# 8161_-FSK_V1_26.net
KiCad netlist of a schematic drawn in Altium Designer
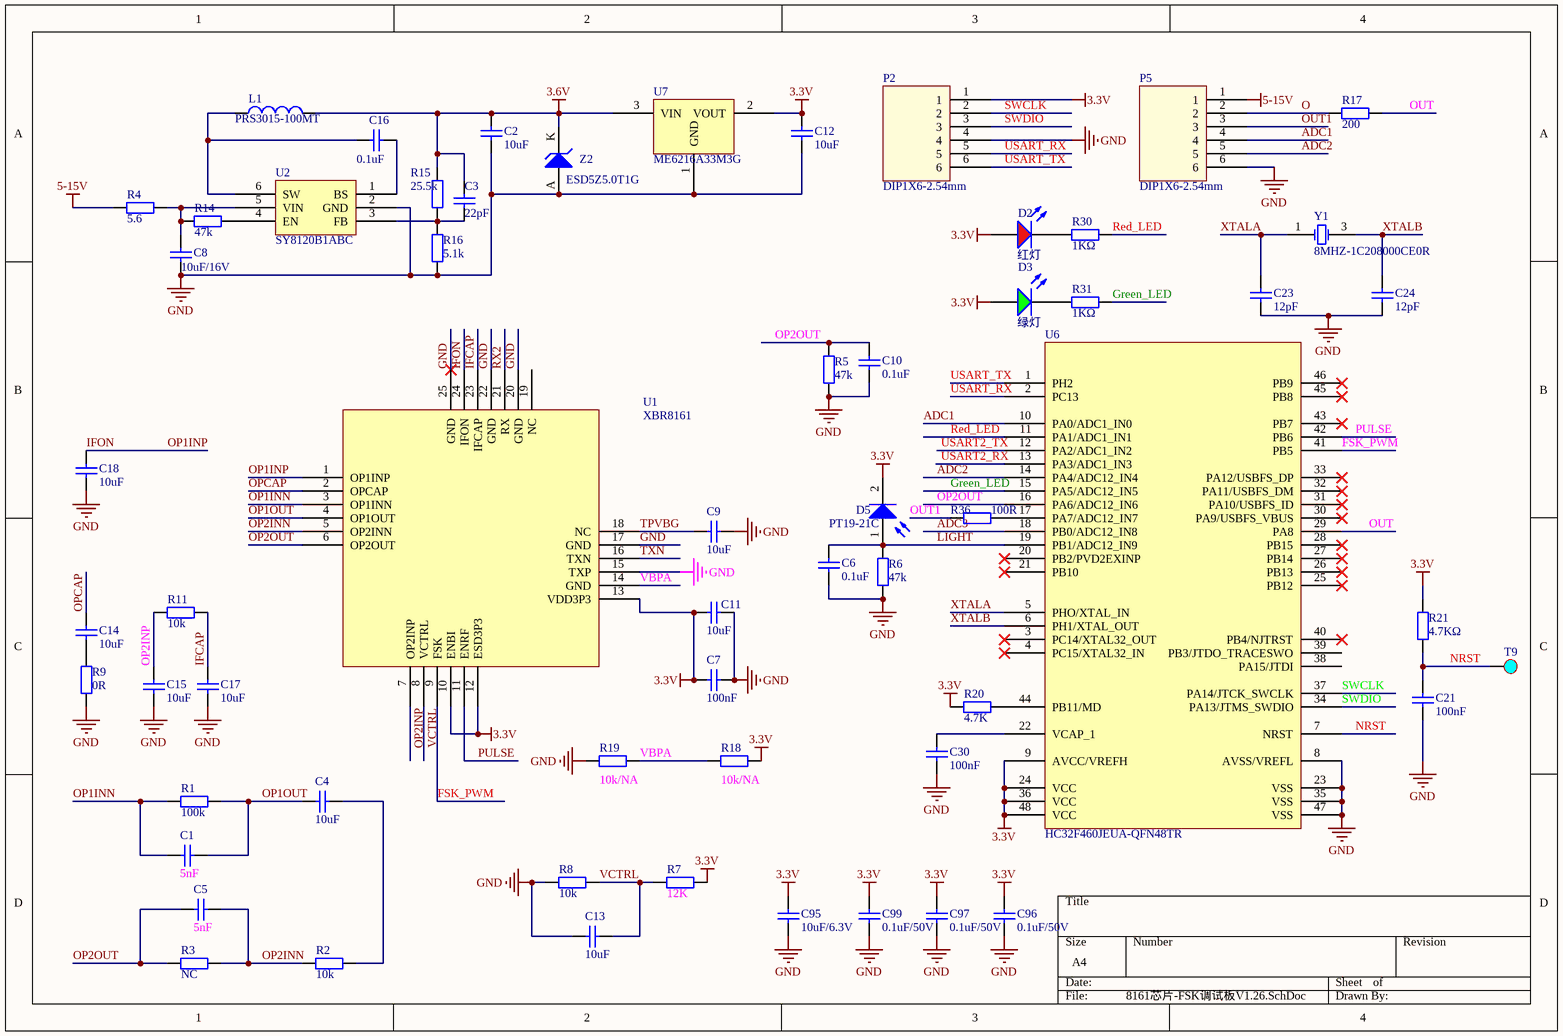
[diagram p0: 8161芯片-FSK调试板V1.26.SchDoc]

(export (version "E")
  (design (tool "Eeschema 10.0.6"))
  (components
    (comp (ref "C1")
      (value "5nF")
      (footprint "C0402")
      (description "Capacitor")
      (fields (field (name "PUBLISHER") "Altium Limited"))
      (libsource (lib "Miscellaneous Devices") (part "Cap"))
    )
    (comp (ref "C2")
      (value "10uF")
      (footprint "C0402")
      (description "Capacitor")
      (fields (field (name "PUBLISHER") "Altium Limited"))
      (libsource (lib "Miscellaneous Devices") (part "Cap"))
    )
    (comp (ref "C3")
      (value "22pF")
      (footprint "C0402")
      (description "Capacitor")
      (fields (field (name "PUBLISHER") "Altium Limited"))
      (libsource (lib "Miscellaneous Devices") (part "Cap"))
    )
    (comp (ref "C4")
      (value "10uF")
      (footprint "C0402")
      (description "Capacitor")
      (fields (field (name "PUBLISHER") "Altium Limited"))
      (libsource (lib "Miscellaneous Devices") (part "Cap"))
    )
    (comp (ref "C5")
      (value "5nF")
      (footprint "C0402")
      (description "Capacitor")
      (fields (field (name "PUBLISHER") "Altium Limited"))
      (libsource (lib "Miscellaneous Devices") (part "Cap"))
    )
    (comp (ref "C6")
      (value "0.1uF")
      (footprint "C0402")
      (description "Capacitor")
      (fields (field (name "PUBLISHER") "Altium Limited"))
      (libsource (lib "Miscellaneous Devices") (part "Cap"))
    )
    (comp (ref "C7")
      (value "100nF")
      (footprint "C0402")
      (description "Capacitor")
      (fields (field (name "PUBLISHER") "Altium Limited"))
      (libsource (lib "Miscellaneous Devices") (part "Cap"))
    )
    (comp (ref "C8")
      (value "10uF/16V")
      (footprint "C0603")
      (description "Capacitor")
      (fields (field (name "PUBLISHER") "Altium Limited"))
      (libsource (lib "Miscellaneous Devices") (part "Cap"))
    )
    (comp (ref "C9")
      (value "10uF")
      (footprint "C0402")
      (description "Capacitor")
      (fields (field (name "PUBLISHER") "Altium Limited"))
      (libsource (lib "Miscellaneous Devices") (part "Cap"))
    )
    (comp (ref "C10")
      (value "0.1uF")
      (footprint "C0402")
      (description "Capacitor")
      (fields (field (name "PUBLISHER") "Altium Limited"))
      (libsource (lib "Miscellaneous Devices") (part "Cap"))
    )
    (comp (ref "C11")
      (value "10uF")
      (footprint "C0402")
      (description "Capacitor")
      (fields (field (name "PUBLISHER") "Altium Limited"))
      (libsource (lib "Miscellaneous Devices") (part "Cap"))
    )
    (comp (ref "C12")
      (value "10uF")
      (footprint "C0402")
      (description "Capacitor")
      (fields (field (name "PUBLISHER") "Altium Limited"))
      (libsource (lib "Miscellaneous Devices") (part "Cap"))
    )
    (comp (ref "C13")
      (value "10uF")
      (footprint "C0402")
      (description "Capacitor")
      (fields (field (name "PUBLISHER") "Altium Limited"))
      (libsource (lib "Miscellaneous Devices") (part "Cap"))
    )
    (comp (ref "C14")
      (value "10uF")
      (footprint "C0402")
      (description "Capacitor")
      (fields (field (name "PUBLISHER") "Altium Limited"))
      (libsource (lib "Miscellaneous Devices") (part "Cap"))
    )
    (comp (ref "C15")
      (value "10uF")
      (footprint "C0402")
      (description "Capacitor")
      (fields (field (name "PUBLISHER") "Altium Limited"))
      (libsource (lib "Miscellaneous Devices") (part "Cap"))
    )
    (comp (ref "C16")
      (value "0.1uF")
      (footprint "C0402")
      (description "Capacitor")
      (fields (field (name "PUBLISHER") "Altium Limited"))
      (libsource (lib "Miscellaneous Devices") (part "Cap"))
    )
    (comp (ref "C17")
      (value "10uF")
      (footprint "C0402")
      (description "Capacitor")
      (fields (field (name "PUBLISHER") "Altium Limited"))
      (libsource (lib "Miscellaneous Devices") (part "Cap"))
    )
    (comp (ref "C18")
      (value "10uF")
      (footprint "C0402")
      (description "Capacitor")
      (fields (field (name "PUBLISHER") "Altium Limited"))
      (libsource (lib "Miscellaneous Devices") (part "Cap"))
    )
    (comp (ref "C21")
      (value "100nF")
      (footprint "C0402")
      (description "贴片电容")
      (libsource (lib "Miscellaneous Devices LC") (part "0402 100nF (104) 10% 16V"))
    )
    (comp (ref "C23")
      (value "12pF")
      (footprint "C0402")
      (description "贴片电容")
      (libsource (lib "Cap") (part "0402 22pF (220) 5% 50V"))
    )
    (comp (ref "C24")
      (value "12pF")
      (footprint "C0402")
      (description "贴片电容")
      (libsource (lib "Cap") (part "0402 22pF (220) 5% 50V"))
    )
    (comp (ref "C30")
      (value "100nF")
      (footprint "C0402")
      (description "Capacitor")
      (fields (field (name "PUBLISHER") "Altium Limited"))
      (libsource (lib "Miscellaneous Devices") (part "Cap"))
    )
    (comp (ref "C95")
      (value "10uF/6.3V")
      (footprint "C0402")
      (description "贴片电容")
      (libsource (lib "Cap") (part "0402 2.2nF (222) 10% 50V"))
    )
    (comp (ref "C96")
      (value "0.1uF/50V")
      (footprint "C0402")
      (description "贴片电容")
      (libsource (lib "Cap") (part "0402 2.2nF (222) 10% 50V"))
    )
    (comp (ref "C97")
      (value "0.1uF/50V")
      (footprint "C0402")
      (description "贴片电容")
      (libsource (lib "Cap") (part "0402 2.2nF (222) 10% 50V"))
    )
    (comp (ref "C99")
      (value "0.1uF/50V")
      (footprint "C0402")
      (description "贴片电容")
      (libsource (lib "Cap") (part "0402 2.2nF (222) 10% 50V"))
    )
    (comp (ref "D2")
      (value "红灯")
      (footprint "LC-0603_LED_S1")
      (description "发光二极管")
      (libsource (lib "Miscellaneous Devices LC") (part "0603 红灯"))
    )
    (comp (ref "D3")
      (value "绿灯")
      (footprint "LC-0603_LED_S1")
      (description "发光二极管")
      (libsource (lib "30x35雷达微动底板V0.2") (part "0603 红灯"))
    )
    (comp (ref "D5")
      (value "PT19-21C")
      (footprint "LED-0603")
      (description "Photosensitive Diode")
      (fields (field (name "PUBLISHER") "Altium Limited"))
      (libsource (lib "Miscellaneous Devices") (part "Photo Sen"))
    )
    (comp (ref "L1")
      (value "PRS3015-100MT")
      (footprint "PRS3015")
      (description "Inductor")
      (fields (field (name "PUBLISHER") "Altium Limited"))
      (libsource (lib "Miscellaneous Devices") (part "Inductor"))
    )
    (comp (ref "P2")
      (value "DIP1X6-2.54mm")
      (footprint "DIP1X6-2.54")
      (libsource (lib "30x35雷达微动底板V0.2") (part "DIP1X6-2.54mm"))
    )
    (comp (ref "P5")
      (value "DIP1X6-2.54mm")
      (footprint "DIP1X6-2.54")
      (libsource (lib "30x35雷达微动底板V0.2") (part "DIP1X6-2.54mm"))
    )
    (comp (ref "R1")
      (value "100k")
      (footprint "R0402")
      (description "Resistor")
      (fields (field (name "PUBLISHER") "Altium Limited"))
      (libsource (lib "") (part "Res2_2"))
    )
    (comp (ref "R2")
      (value "10k")
      (footprint "R0402")
      (description "Resistor")
      (fields (field (name "PUBLISHER") "Altium Limited"))
      (libsource (lib "Miscellaneous Devices") (part "Res2"))
    )
    (comp (ref "R3")
      (value "NC")
      (footprint "R0402")
      (description "Resistor")
      (fields (field (name "PUBLISHER") "Altium Limited"))
      (libsource (lib "Miscellaneous Devices") (part "Res2"))
    )
    (comp (ref "R4")
      (value "5.6")
      (footprint "R0402")
      (description "Resistor")
      (fields (field (name "PUBLISHER") "Altium Limited"))
      (libsource (lib "") (part "Res2_3"))
    )
    (comp (ref "R5")
      (value "47k")
      (footprint "R0402")
      (description "Resistor")
      (fields (field (name "PUBLISHER") "Altium Limited"))
      (libsource (lib "") (part "Res2_1"))
    )
    (comp (ref "R6")
      (value "47k")
      (footprint "R0402")
      (description "Resistor")
      (fields (field (name "PUBLISHER") "Altium Limited"))
      (libsource (lib "") (part "Res2_1"))
    )
    (comp (ref "R7")
      (value "12K")
      (footprint "R0402")
      (description "Resistor")
      (fields (field (name "PUBLISHER") "Altium Limited"))
      (libsource (lib "Miscellaneous Devices") (part "Res2"))
    )
    (comp (ref "R8")
      (value "10k")
      (footprint "R0402")
      (description "Resistor")
      (fields (field (name "PUBLISHER") "Altium Limited"))
      (libsource (lib "Miscellaneous Devices") (part "Res2"))
    )
    (comp (ref "R9")
      (value "0R")
      (footprint "R0402")
      (description "Resistor")
      (fields (field (name "PUBLISHER") "Altium Limited"))
      (libsource (lib "") (part "Res2_1"))
    )
    (comp (ref "R11")
      (value "10k")
      (footprint "R0402")
      (description "Resistor")
      (fields (field (name "PUBLISHER") "Altium Limited"))
      (libsource (lib "Miscellaneous Devices") (part "Res2"))
    )
    (comp (ref "R14")
      (value "47k")
      (footprint "R0402")
      (description "Resistor")
      (fields (field (name "PUBLISHER") "Altium Limited"))
      (libsource (lib "Miscellaneous Devices") (part "Res2"))
    )
    (comp (ref "R15")
      (value "25.5k")
      (footprint "R0402")
      (description "Resistor")
      (fields (field (name "PUBLISHER") "Altium Limited"))
      (libsource (lib "") (part "Res2_4"))
    )
    (comp (ref "R16")
      (value "5.1k")
      (footprint "R0402")
      (description "Resistor")
      (fields (field (name "PUBLISHER") "Altium Limited"))
      (libsource (lib "") (part "Res2_4"))
    )
    (comp (ref "R17")
      (value "200")
      (footprint "R0402")
      (description "Resistor")
      (fields (field (name "PUBLISHER") "Altium Limited"))
      (libsource (lib "") (part "Res2_2"))
    )
    (comp (ref "R18")
      (value "10k/NA")
      (footprint "R0402")
      (description "Resistor")
      (fields (field (name "PUBLISHER") "Altium Limited"))
      (libsource (lib "Miscellaneous Devices") (part "Res2"))
    )
    (comp (ref "R19")
      (value "10k/NA")
      (footprint "R0402")
      (description "Resistor")
      (fields (field (name "PUBLISHER") "Altium Limited"))
      (libsource (lib "Miscellaneous Devices") (part "Res2"))
    )
    (comp (ref "R20")
      (value "4.7K")
      (footprint "R0402")
      (description "Resistor")
      (fields (field (name "PUBLISHER") "Altium Limited"))
      (libsource (lib "") (part "Res2_2"))
    )
    (comp (ref "R21")
      (value "4.7KΩ")
      (footprint "R0402")
      (description "贴片电阻")
      (libsource (lib "") (part "0402 4.7KΩ (4701) 1%_1"))
    )
    (comp (ref "R30")
      (value "1KΩ")
      (footprint "R0402")
      (description "贴片电阻")
      (libsource (lib "Miscellaneous Devices LC") (part "0402 1KΩ (1001) 1%"))
    )
    (comp (ref "R31")
      (value "1KΩ")
      (footprint "R0402")
      (description "贴片电阻")
      (libsource (lib "Miscellaneous Devices LC") (part "0402 1KΩ (1001) 1%"))
    )
    (comp (ref "R36")
      (value "100R")
      (footprint "R0402")
      (description "贴片电阻")
      (libsource (lib "Miscellaneous Devices LC") (part "0402 4.7KΩ (4701) 1%"))
    )
    (comp (ref "T9")
      (value "~")
      (footprint "TestPoints")
      (description "TestPoints")
      (libsource (lib "标准原理图库（特种板）") (part "TestPoints"))
    )
    (comp (ref "U1")
      (value "XBR8161")
      (footprint "QFN24")
      (libsource (lib "altium-import") (part "root_0_XBR8161_"))
    )
    (comp (ref "U2") (value "SY8120B1ABC") (footprint "SOT-23-6") (libsource (lib "Schlib1") (part "H9108")))
    (comp (ref "U6")
      (value "HC32F460JEUA-QFN48TR")
      (footprint "QFN48-5X5mm")
      (libsource (lib "LD-ShouShi-Module-V1.0") (part "HC32F460JETA-LQFP48"))
    )
    (comp (ref "U7")
      (value "ME6216A33M3G")
      (footprint "SOT-23-L")
      (libsource (lib "Schlib1") (part "SSP6206"))
    )
    (comp (ref "Y1")
      (value "8MHZ-1C208000CE0R")
      (footprint "OSC-SMD_3225")
      (description "贴片晶振")
      (libsource (lib "CrystalOscillator") (part "SMD-3225_4P  25MHZ 12PF 10PPM"))
    )
    (comp (ref "Z2")
      (value "ESD5Z5.0T1G")
      (footprint "SOD323")
      (description "Zener Diode")
      (fields (field (name "PUBLISHER") "Altium Limited"))
      (libsource (lib "Miscellaneous Devices") (part "D Zener"))
    )
  )
  (nets
    (net (code "1") (name "/ADC1") (class "Default")
      (node (ref "P5") (pin "4") (pinfunction "4_4") (pintype "passive"))
      (node (ref "U6") (pin "10") (pinfunction "PA0/ADC1_IN0_10") (pintype "passive"))
    )
    (net (code "2") (name "/ADC2") (class "Default")
      (node (ref "P5") (pin "5") (pinfunction "5_5") (pintype "passive"))
      (node (ref "U6") (pin "14") (pinfunction "PA4/ADC12_IN4_14") (pintype "passive"))
    )
    (net (code "3") (name "/ADC3") (class "Default")
      (node (ref "U6") (pin "18") (pinfunction "PB0/ADC12_IN8_18") (pintype "passive"))
    )
    (net (code "4") (name "/FSK_PWM") (class "Default")
      (node (ref "U1") (pin "9") (pinfunction "FSK_9") (pintype "passive"))
      (node (ref "U6") (pin "41") (pinfunction "PB5_41") (pintype "passive"))
    )
    (net (code "5") (name "/Green_LED") (class "Default")
      (node (ref "R31") (pin "1") (pinfunction "1_1") (pintype "passive"))
      (node (ref "U6") (pin "15") (pinfunction "PA5/ADC12_IN5_15") (pintype "passive"))
    )
    (net (code "6") (name "/IFCAP") (class "Default")
      (node (ref "C17") (pin "2") (pinfunction "2_2") (pintype "passive"))
      (node (ref "R11") (pin "1") (pinfunction "1_1") (pintype "passive"))
      (node (ref "U1") (pin "23") (pinfunction "IFCAP_23") (pintype "passive"))
    )
    (net (code "7") (name "/IFON") (class "Default")
      (node (ref "C18") (pin "2") (pinfunction "2_2") (pintype "passive"))
      (node (ref "U1") (pin "1") (pinfunction "OP1INP_1") (pintype "passive"))
      (node (ref "U1") (pin "24") (pinfunction "IFON_24") (pintype "passive"))
    )
    (net (code "8") (name "/LIGHT") (class "Default")
      (node (ref "C6") (pin "1") (pinfunction "1_1") (pintype "passive"))
      (node (ref "D5") (pin "1") (pinfunction "A_1") (pintype "passive"))
      (node (ref "R6") (pin "1") (pinfunction "1_1") (pintype "passive"))
      (node (ref "U6") (pin "19") (pinfunction "PB1/ADC12_IN9_19") (pintype "passive"))
    )
    (net (code "9") (name "/NRST") (class "Default")
      (node (ref "C21") (pin "2") (pinfunction "2_2") (pintype "passive"))
      (node (ref "R21") (pin "1") (pinfunction "1_1") (pintype "passive"))
      (node (ref "T9") (pin "1") (pinfunction "1_1") (pintype "passive"))
      (node (ref "U6") (pin "7") (pinfunction "NRST_7") (pintype "passive"))
    )
    (net (code "10") (name "/O") (class "Default")
      (node (ref "P5") (pin "2") (pinfunction "2_2") (pintype "passive"))
      (node (ref "R17") (pin "1") (pinfunction "1_1") (pintype "passive"))
    )
    (net (code "11") (name "/OP1INN") (class "Default")
      (node (ref "C1") (pin "2") (pinfunction "2_2") (pintype "passive"))
      (node (ref "R1") (pin "1") (pinfunction "1_1") (pintype "passive"))
      (node (ref "U1") (pin "3") (pinfunction "OP1INN_3") (pintype "passive"))
    )
    (net (code "12") (name "/OP1OUT") (class "Default")
      (node (ref "C1") (pin "1") (pinfunction "1_1") (pintype "passive"))
      (node (ref "C4") (pin "2") (pinfunction "2_2") (pintype "passive"))
      (node (ref "R1") (pin "2") (pinfunction "2_2") (pintype "passive"))
      (node (ref "U1") (pin "4") (pinfunction "OP1OUT_4") (pintype "passive"))
    )
    (net (code "13") (name "/OP2INN") (class "Default")
      (node (ref "C5") (pin "2") (pinfunction "2_2") (pintype "passive"))
      (node (ref "R2") (pin "2") (pinfunction "2_2") (pintype "passive"))
      (node (ref "R3") (pin "1") (pinfunction "1_1") (pintype "passive"))
      (node (ref "U1") (pin "5") (pinfunction "OP2INN_5") (pintype "passive"))
    )
    (net (code "14") (name "/OP2INP") (class "Default")
      (node (ref "C15") (pin "1") (pinfunction "1_1") (pintype "passive"))
      (node (ref "R11") (pin "2") (pinfunction "2_2") (pintype "passive"))
      (node (ref "U1") (pin "7") (pinfunction "OP2INP_7") (pintype "passive"))
    )
    (net (code "15") (name "/OP2OUT") (class "Default")
      (node (ref "C10") (pin "1") (pinfunction "1_1") (pintype "passive"))
      (node (ref "C5") (pin "1") (pinfunction "1_1") (pintype "passive"))
      (node (ref "R3") (pin "2") (pinfunction "2_2") (pintype "passive"))
      (node (ref "R5") (pin "1") (pinfunction "1_1") (pintype "passive"))
      (node (ref "U1") (pin "6") (pinfunction "OP2OUT_6") (pintype "passive"))
      (node (ref "U6") (pin "16") (pinfunction "PA6/ADC12_IN6_16") (pintype "passive"))
    )
    (net (code "16") (name "/OPCAP") (class "Default")
      (node (ref "C14") (pin "2") (pinfunction "2_2") (pintype "passive"))
      (node (ref "U1") (pin "2") (pinfunction "OPCAP_2") (pintype "passive"))
    )
    (net (code "17") (name "/OUT") (class "Default")
      (node (ref "R17") (pin "2") (pinfunction "2_2") (pintype "passive"))
      (node (ref "U6") (pin "29") (pinfunction "PA8_29") (pintype "passive"))
    )
    (net (code "18") (name "/OUT1") (class "Default")
      (node (ref "P5") (pin "3") (pinfunction "3_3") (pintype "passive"))
      (node (ref "R36") (pin "2") (pinfunction "2_2") (pintype "passive"))
    )
    (net (code "19") (name "/PULSE") (class "Default")
      (node (ref "U1") (pin "11") (pinfunction "ENRF_11") (pintype "passive"))
      (node (ref "U6") (pin "42") (pinfunction "PB6_42") (pintype "passive"))
    )
    (net (code "20") (name "/RX2") (class "Default")
      (node (ref "U1") (pin "21") (pinfunction "RX_21") (pintype "passive"))
    )
    (net (code "21") (name "/Red_LED") (class "Default")
      (node (ref "R30") (pin "1") (pinfunction "1_1") (pintype "passive"))
      (node (ref "U6") (pin "11") (pinfunction "PA1/ADC1_IN1_11") (pintype "passive"))
    )
    (net (code "22") (name "/SWCLK") (class "Default")
      (node (ref "P2") (pin "2") (pinfunction "2_2") (pintype "passive"))
      (node (ref "U6") (pin "37") (pinfunction "PA14/JTCK_SWCLK_37") (pintype "passive"))
    )
    (net (code "23") (name "/SWDIO") (class "Default")
      (node (ref "P2") (pin "3") (pinfunction "3_3") (pintype "passive"))
      (node (ref "U6") (pin "34") (pinfunction "PA13/JTMS_SWDIO_34") (pintype "passive"))
    )
    (net (code "24") (name "/TPVBG") (class "Default")
      (node (ref "C9") (pin "2") (pinfunction "2_2") (pintype "passive"))
      (node (ref "U1") (pin "18") (pinfunction "NC_18") (pintype "passive"))
    )
    (net (code "25") (name "/TXN") (class "Default")
      (node (ref "U1") (pin "16") (pinfunction "TXN_16") (pintype "passive"))
    )
    (net (code "26") (name "/USART2_RX") (class "Default")
      (node (ref "U6") (pin "13") (pinfunction "PA3/ADC1_IN3_13") (pintype "passive"))
    )
    (net (code "27") (name "/USART2_TX") (class "Default")
      (node (ref "U6") (pin "12") (pinfunction "PA2/ADC1_IN2_12") (pintype "passive"))
    )
    (net (code "28") (name "/USART_RX") (class "Default")
      (node (ref "P2") (pin "5") (pinfunction "5_5") (pintype "passive"))
      (node (ref "U6") (pin "2") (pinfunction "PC13_2") (pintype "passive"))
    )
    (net (code "29") (name "/USART_TX") (class "Default")
      (node (ref "P2") (pin "6") (pinfunction "6_6") (pintype "passive"))
      (node (ref "U6") (pin "1") (pinfunction "PH2_1") (pintype "passive"))
    )
    (net (code "30") (name "/VBPA") (class "Default")
      (node (ref "R18") (pin "2") (pinfunction "2_2") (pintype "passive"))
      (node (ref "R19") (pin "1") (pinfunction "1_1") (pintype "passive"))
      (node (ref "U1") (pin "14") (pinfunction "GND_14") (pintype "passive"))
    )
    (net (code "31") (name "/VCTRL") (class "Default")
      (node (ref "C13") (pin "1") (pinfunction "1_1") (pintype "passive"))
      (node (ref "R7") (pin "2") (pinfunction "2_2") (pintype "passive"))
      (node (ref "R8") (pin "1") (pinfunction "1_1") (pintype "passive"))
      (node (ref "U1") (pin "8") (pinfunction "VCTRL_8") (pintype "passive"))
    )
    (net (code "32") (name "/XTALA") (class "Default")
      (node (ref "C23") (pin "2") (pinfunction "2_2") (pintype "passive"))
      (node (ref "U6") (pin "5") (pinfunction "PHO/XTAL_IN_5") (pintype "passive"))
      (node (ref "Y1") (pin "1") (pinfunction "OSC1_1") (pintype "passive"))
    )
    (net (code "33") (name "/XTALB") (class "Default")
      (node (ref "C24") (pin "2") (pinfunction "2_2") (pintype "passive"))
      (node (ref "U6") (pin "6") (pinfunction "PH1/XTAL_OUT_6") (pintype "passive"))
      (node (ref "Y1") (pin "3") (pinfunction "OSC2_3") (pintype "passive"))
    )
    (net (code "34") (name "3.3V") (class "Default")
      (node (ref "C11") (pin "2") (pinfunction "2_2") (pintype "passive"))
      (node (ref "C12") (pin "1") (pinfunction "1_1") (pintype "passive"))
      (node (ref "C7") (pin "2") (pinfunction "2_2") (pintype "passive"))
      (node (ref "C95") (pin "1") (pinfunction "1_1") (pintype "passive"))
      (node (ref "C96") (pin "1") (pinfunction "1_1") (pintype "passive"))
      (node (ref "C97") (pin "1") (pinfunction "1_1") (pintype "passive"))
      (node (ref "C99") (pin "1") (pinfunction "1_1") (pintype "passive"))
      (node (ref "D2") (pin "A") (pinfunction "A_A") (pintype "passive"))
      (node (ref "D3") (pin "A") (pinfunction "A_A") (pintype "passive"))
      (node (ref "D5") (pin "2") (pinfunction "K_2") (pintype "passive"))
      (node (ref "P2") (pin "1") (pinfunction "1_1") (pintype "passive"))
      (node (ref "R18") (pin "1") (pinfunction "1_1") (pintype "passive"))
      (node (ref "R20") (pin "1") (pinfunction "1_1") (pintype "passive"))
      (node (ref "R21") (pin "2") (pinfunction "2_2") (pintype "passive"))
      (node (ref "R7") (pin "1") (pinfunction "1_1") (pintype "passive"))
      (node (ref "U1") (pin "10") (pinfunction "ENBI_10") (pintype "passive"))
      (node (ref "U1") (pin "12") (pinfunction "ESD3P3_12") (pintype "passive"))
      (node (ref "U1") (pin "13") (pinfunction "VDD3P3_13") (pintype "passive"))
      (node (ref "U6") (pin "24") (pinfunction "VCC_24") (pintype "passive"))
      (node (ref "U6") (pin "36") (pinfunction "VCC_36") (pintype "passive"))
      (node (ref "U6") (pin "48") (pinfunction "VCC_48") (pintype "passive"))
      (node (ref "U6") (pin "9") (pinfunction "AVCC/VREFH_9") (pintype "passive"))
      (node (ref "U7") (pin "2") (pinfunction "VOUT_2") (pintype "passive"))
    )
    (net (code "35") (name "3.6V") (class "Default")
      (node (ref "C2") (pin "1") (pinfunction "1_1") (pintype "passive"))
      (node (ref "C3") (pin "2") (pinfunction "2_2") (pintype "passive"))
      (node (ref "L1") (pin "2") (pinfunction "2_2") (pintype "passive"))
      (node (ref "R15") (pin "2") (pinfunction "2_2") (pintype "passive"))
      (node (ref "U7") (pin "3") (pinfunction "VIN_3") (pintype "passive"))
      (node (ref "Z2") (pin "K") (pinfunction "K_K") (pintype "passive"))
    )
    (net (code "36") (name "5-15V") (class "Default")
      (node (ref "P5") (pin "1") (pinfunction "1_1") (pintype "passive"))
      (node (ref "R4") (pin "1") (pinfunction "1_1") (pintype "passive"))
    )
    (net (code "37") (name "GND") (class "Default")
      (node (ref "C10") (pin "2") (pinfunction "2_2") (pintype "passive"))
      (node (ref "C11") (pin "1") (pinfunction "1_1") (pintype "passive"))
      (node (ref "C12") (pin "2") (pinfunction "2_2") (pintype "passive"))
      (node (ref "C13") (pin "2") (pinfunction "2_2") (pintype "passive"))
      (node (ref "C15") (pin "2") (pinfunction "2_2") (pintype "passive"))
      (node (ref "C17") (pin "1") (pinfunction "1_1") (pintype "passive"))
      (node (ref "C18") (pin "1") (pinfunction "1_1") (pintype "passive"))
      (node (ref "C2") (pin "2") (pinfunction "2_2") (pintype "passive"))
      (node (ref "C21") (pin "1") (pinfunction "1_1") (pintype "passive"))
      (node (ref "C23") (pin "1") (pinfunction "1_1") (pintype "passive"))
      (node (ref "C24") (pin "1") (pinfunction "1_1") (pintype "passive"))
      (node (ref "C30") (pin "2") (pinfunction "2_2") (pintype "passive"))
      (node (ref "C6") (pin "2") (pinfunction "2_2") (pintype "passive"))
      (node (ref "C7") (pin "1") (pinfunction "1_1") (pintype "passive"))
      (node (ref "C8") (pin "2") (pinfunction "2_2") (pintype "passive"))
      (node (ref "C9") (pin "1") (pinfunction "1_1") (pintype "passive"))
      (node (ref "C95") (pin "2") (pinfunction "2_2") (pintype "passive"))
      (node (ref "C96") (pin "2") (pinfunction "2_2") (pintype "passive"))
      (node (ref "C97") (pin "2") (pinfunction "2_2") (pintype "passive"))
      (node (ref "C99") (pin "2") (pinfunction "2_2") (pintype "passive"))
      (node (ref "P2") (pin "4") (pinfunction "4_4") (pintype "passive"))
      (node (ref "P5") (pin "6") (pinfunction "6_6") (pintype "passive"))
      (node (ref "R16") (pin "1") (pinfunction "1_1") (pintype "passive"))
      (node (ref "R19") (pin "2") (pinfunction "2_2") (pintype "passive"))
      (node (ref "R5") (pin "2") (pinfunction "2_2") (pintype "passive"))
      (node (ref "R6") (pin "2") (pinfunction "2_2") (pintype "passive"))
      (node (ref "R8") (pin "2") (pinfunction "2_2") (pintype "passive"))
      (node (ref "R9") (pin "2") (pinfunction "2_2") (pintype "passive"))
      (node (ref "U1") (pin "15") (pinfunction "TXP_15") (pintype "passive"))
      (node (ref "U1") (pin "17") (pinfunction "GND_17") (pintype "passive"))
      (node (ref "U1") (pin "20") (pinfunction "GND_20") (pintype "passive"))
      (node (ref "U1") (pin "22") (pinfunction "GND_22") (pintype "passive"))
      (node (ref "U1") (pin "25") (pinfunction "GND_25") (pintype "passive"))
      (node (ref "U2") (pin "2") (pinfunction "GND_2") (pintype "passive"))
      (node (ref "U6") (pin "23") (pinfunction "VSS_23") (pintype "passive"))
      (node (ref "U6") (pin "35") (pinfunction "VSS_35") (pintype "passive"))
      (node (ref "U6") (pin "47") (pinfunction "VSS_47") (pintype "passive"))
      (node (ref "U6") (pin "8") (pinfunction "AVSS/VREFL_8") (pintype "passive"))
      (node (ref "U7") (pin "1") (pinfunction "GND_1") (pintype "passive"))
      (node (ref "Z2") (pin "A") (pinfunction "A_A") (pintype "passive"))
    )
    (net (code "38") (name "Net-(C4-Pad1)") (class "Default")
      (node (ref "C4") (pin "1") (pinfunction "1_1") (pintype "passive"))
      (node (ref "R2") (pin "1") (pinfunction "1_1") (pintype "passive"))
    )
    (net (code "39") (name "Net-(C14-Pad1)") (class "Default")
      (node (ref "C14") (pin "1") (pinfunction "1_1") (pintype "passive"))
      (node (ref "R9") (pin "1") (pinfunction "1_1") (pintype "passive"))
    )
    (net (code "40") (name "Net-(D2-PadK)") (class "Default")
      (node (ref "D2") (pin "K") (pinfunction "K_K") (pintype "passive"))
      (node (ref "R30") (pin "2") (pinfunction "2_2") (pintype "passive"))
    )
    (net (code "41") (name "Net-(D3-PadK)") (class "Default")
      (node (ref "D3") (pin "K") (pinfunction "K_K") (pintype "passive"))
      (node (ref "R31") (pin "2") (pinfunction "2_2") (pintype "passive"))
    )
    (net (code "42") (name "Net-(U2-BS)") (class "Default")
      (node (ref "C16") (pin "2") (pinfunction "2_2") (pintype "passive"))
      (node (ref "U2") (pin "1") (pinfunction "BS_1") (pintype "passive"))
    )
    (net (code "43") (name "Net-(U2-EN)") (class "Default")
      (node (ref "R14") (pin "1") (pinfunction "1_1") (pintype "passive"))
      (node (ref "U2") (pin "4") (pinfunction "EN_4") (pintype "passive"))
    )
    (net (code "44") (name "Net-(U2-FB)") (class "Default")
      (node (ref "C3") (pin "1") (pinfunction "1_1") (pintype "passive"))
      (node (ref "R15") (pin "1") (pinfunction "1_1") (pintype "passive"))
      (node (ref "R16") (pin "2") (pinfunction "2_2") (pintype "passive"))
      (node (ref "U2") (pin "3") (pinfunction "FB_3") (pintype "passive"))
    )
    (net (code "45") (name "Net-(U2-SW)") (class "Default")
      (node (ref "C16") (pin "1") (pinfunction "1_1") (pintype "passive"))
      (node (ref "L1") (pin "1") (pinfunction "1_1") (pintype "passive"))
      (node (ref "U2") (pin "6") (pinfunction "SW_6") (pintype "passive"))
    )
    (net (code "46") (name "Net-(U2-VIN)") (class "Default")
      (node (ref "C8") (pin "1") (pinfunction "1_1") (pintype "passive"))
      (node (ref "R14") (pin "2") (pinfunction "2_2") (pintype "passive"))
      (node (ref "R4") (pin "2") (pinfunction "2_2") (pintype "passive"))
      (node (ref "U2") (pin "5") (pinfunction "VIN_5") (pintype "passive"))
    )
    (net (code "47") (name "Net-(U6-PA7{slash}ADC12_IN7)") (class "Default")
      (node (ref "R36") (pin "1") (pinfunction "1_1") (pintype "passive"))
      (node (ref "U6") (pin "17") (pinfunction "PA7/ADC12_IN7_17") (pintype "passive"))
    )
    (net (code "48") (name "Net-(U6-PB11{slash}MD)") (class "Default")
      (node (ref "R20") (pin "2") (pinfunction "2_2") (pintype "passive"))
      (node (ref "U6") (pin "44") (pinfunction "PB11/MD_44") (pintype "passive"))
    )
    (net (code "49") (name "Net-(U6-VCAP_1)") (class "Default")
      (node (ref "C30") (pin "1") (pinfunction "1_1") (pintype "passive"))
      (node (ref "U6") (pin "22") (pinfunction "VCAP_1_22") (pintype "passive"))
    )
    (net (code "50") (name "unconnected-(U1-NC-Pad19)") (class "Default")
      (node (ref "U1") (pin "19") (pinfunction "NC_19") (pintype "passive"))
    )
    (net (code "51") (name "unconnected-(U6-PA9{slash}USBFS_VBUS-Pad30)") (class "Default")
      (node (ref "U6") (pin "30") (pinfunction "PA9/USBFS_VBUS_30") (pintype "passive+no_connect"))
    )
    (net (code "52") (name "unconnected-(U6-PA10{slash}USBFS_ID-Pad31)") (class "Default")
      (node (ref "U6") (pin "31") (pinfunction "PA10/USBFS_ID_31") (pintype "passive+no_connect"))
    )
    (net (code "53") (name "unconnected-(U6-PA11{slash}USBFS_DM-Pad32)") (class "Default")
      (node (ref "U6") (pin "32") (pinfunction "PA11/USBFS_DM_32") (pintype "passive+no_connect"))
    )
    (net (code "54") (name "unconnected-(U6-PA12{slash}USBFS_DP-Pad33)") (class "Default")
      (node (ref "U6") (pin "33") (pinfunction "PA12/USBFS_DP_33") (pintype "passive+no_connect"))
    )
    (net (code "55") (name "unconnected-(U6-PA15{slash}JTDI-Pad38)") (class "Default")
      (node (ref "U6") (pin "38") (pinfunction "PA15/JTDI_38") (pintype "passive"))
    )
    (net (code "56") (name "unconnected-(U6-PB2{slash}PVD2EXINP-Pad20)") (class "Default")
      (node (ref "U6") (pin "20") (pinfunction "PB2/PVD2EXINP_20") (pintype "passive+no_connect"))
    )
    (net (code "57") (name "unconnected-(U6-PB3{slash}JTDO_TRACESWO-Pad39)") (class "Default")
      (node (ref "U6") (pin "39") (pinfunction "PB3/JTDO_TRACESWO_39") (pintype "passive"))
    )
    (net (code "58") (name "unconnected-(U6-PB4{slash}NJTRST-Pad40)") (class "Default")
      (node (ref "U6") (pin "40") (pinfunction "PB4/NJTRST_40") (pintype "passive+no_connect"))
    )
    (net (code "59") (name "unconnected-(U6-PB7-Pad43)") (class "Default")
      (node (ref "U6") (pin "43") (pinfunction "PB7_43") (pintype "passive+no_connect"))
    )
    (net (code "60") (name "unconnected-(U6-PB8-Pad45)") (class "Default")
      (node (ref "U6") (pin "45") (pinfunction "PB8_45") (pintype "passive+no_connect"))
    )
    (net (code "61") (name "unconnected-(U6-PB9-Pad46)") (class "Default")
      (node (ref "U6") (pin "46") (pinfunction "PB9_46") (pintype "passive+no_connect"))
    )
    (net (code "62") (name "unconnected-(U6-PB10-Pad21)") (class "Default")
      (node (ref "U6") (pin "21") (pinfunction "PB10_21") (pintype "passive+no_connect"))
    )
    (net (code "63") (name "unconnected-(U6-PB12-Pad25)") (class "Default")
      (node (ref "U6") (pin "25") (pinfunction "PB12_25") (pintype "passive+no_connect"))
    )
    (net (code "64") (name "unconnected-(U6-PB13-Pad26)") (class "Default")
      (node (ref "U6") (pin "26") (pinfunction "PB13_26") (pintype "passive+no_connect"))
    )
    (net (code "65") (name "unconnected-(U6-PB14-Pad27)") (class "Default")
      (node (ref "U6") (pin "27") (pinfunction "PB14_27") (pintype "passive+no_connect"))
    )
    (net (code "66") (name "unconnected-(U6-PB15-Pad28)") (class "Default")
      (node (ref "U6") (pin "28") (pinfunction "PB15_28") (pintype "passive+no_connect"))
    )
    (net (code "67") (name "unconnected-(U6-PC14{slash}XTAL32_OUT-Pad3)") (class "Default")
      (node (ref "U6") (pin "3") (pinfunction "PC14/XTAL32_OUT_3") (pintype "passive+no_connect"))
    )
    (net (code "68") (name "unconnected-(U6-PC15{slash}XTAL32_IN-Pad4)") (class "Default")
      (node (ref "U6") (pin "4") (pinfunction "PC15/XTAL32_IN_4") (pintype "passive+no_connect"))
    )
  )
)
